# esquematico.net
KiCad netlist of a schematic drawn in EAGLE
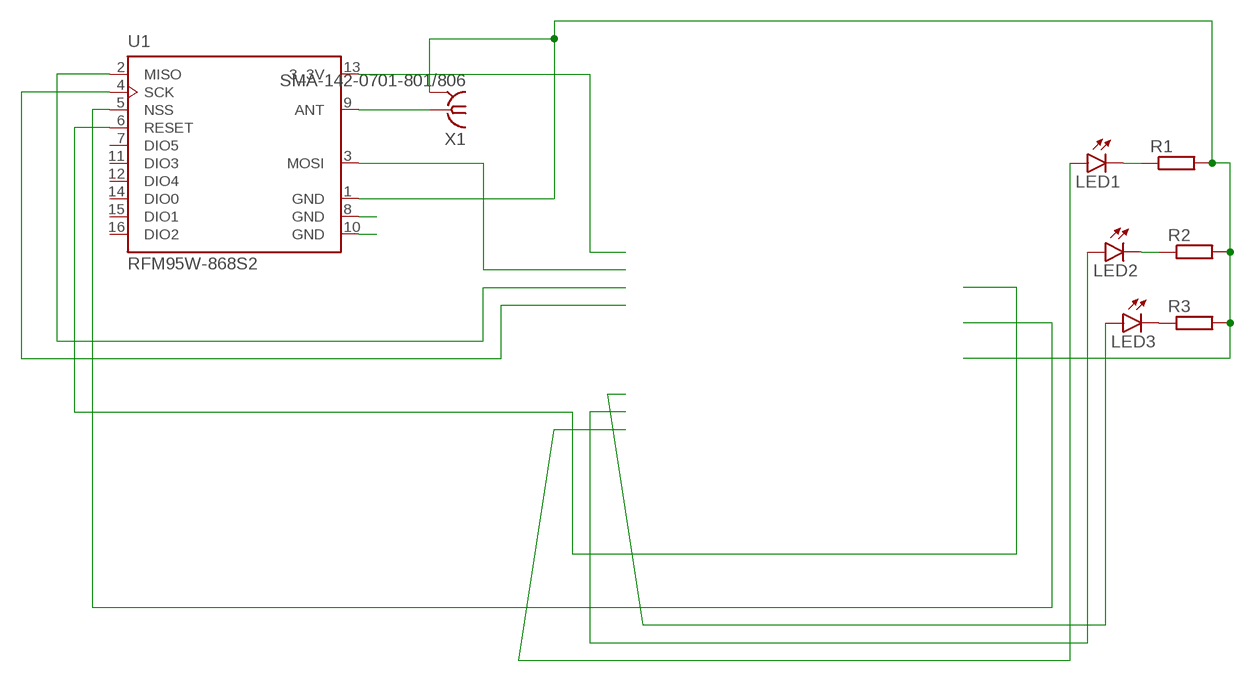
[diagram p0: schematic, sheet 1]

(export (version "E")
  (design (tool "Eeschema 10.0.6"))
  (components
    (comp (ref "LED1")
      (value "LED3MM")
      (footprint "eagle-import:LED3MM")
      (libsource (lib "eagle-import") (part "LED3MM"))
    )
    (comp (ref "LED2")
      (value "LED3MM")
      (footprint "eagle-import:LED3MM")
      (libsource (lib "eagle-import") (part "LED3MM"))
    )
    (comp (ref "LED3")
      (value "LED3MM")
      (footprint "eagle-import:LED3MM")
      (libsource (lib "eagle-import") (part "LED3MM"))
    )
    (comp (ref "R1")
      (value "R-EU_M0805")
      (footprint "eagle-import:M0805")
      (libsource (lib "eagle-import") (part "R-EU_M0805"))
    )
    (comp (ref "R2")
      (value "R-EU_M0805")
      (footprint "eagle-import:M0805")
      (libsource (lib "eagle-import") (part "R-EU_M0805"))
    )
    (comp (ref "R3")
      (value "R-EU_M0805")
      (footprint "eagle-import:M0805")
      (libsource (lib "eagle-import") (part "R-EU_M0805"))
    )
    (comp (ref "U1")
      (value "RFM95W-868S2")
      (footprint "eagle-import:XCVR_RFM95W-868S2")
      (fields (field (name "MF") "RF"))
      (libsource (lib "eagle-import") (part "RFM95W-868S2"))
    )
    (comp (ref "X1")
      (value "SMA-142-0701-801/806")
      (footprint "eagle-import:J502-ND-142-0701-801_806")
      (fields (field (name "MF") "JOHNSON COMPONENTS") (field (name "MPN") "142-0701-801"))
      (libsource (lib "eagle-import") (part "SMA-142-0701-801/806"))
    )
  )
  (nets
    (net (code "1") (name "Net-(LED1-C)") (class "Default")
      (node (ref "LED1") (pin "K") (pinfunction "C_K") (pintype "passive"))
      (node (ref "R1") (pin "1") (pinfunction "1_1") (pintype "passive"))
    )
    (net (code "2") (name "Net-(LED2-C)") (class "Default")
      (node (ref "LED2") (pin "K") (pinfunction "C_K") (pintype "passive"))
      (node (ref "R2") (pin "1") (pinfunction "1_1") (pintype "passive"))
    )
    (net (code "3") (name "Net-(LED3-C)") (class "Default")
      (node (ref "LED3") (pin "K") (pinfunction "C_K") (pintype "passive"))
      (node (ref "R3") (pin "1") (pinfunction "1_1") (pintype "passive"))
    )
    (net (code "4") (name "Net-(R1-Pad2)") (class "Default")
      (node (ref "R1") (pin "2") (pinfunction "2_2") (pintype "passive"))
      (node (ref "R2") (pin "2") (pinfunction "2_2") (pintype "passive"))
      (node (ref "R3") (pin "2") (pinfunction "2_2") (pintype "passive"))
      (node (ref "U1") (pin "1") (pinfunction "GND_1") (pintype "power_in"))
      (node (ref "X1") (pin "G@1") (pinfunction "2_G@1") (pintype "passive"))
      (node (ref "X1") (pin "G@2") (pinfunction "2_G@2") (pintype "passive"))
      (node (ref "X1") (pin "G@3") (pinfunction "2_G@3") (pintype "passive"))
      (node (ref "X1") (pin "G@4") (pinfunction "2_G@4") (pintype "passive"))
    )
    (net (code "5") (name "Net-(U1-ANT)") (class "Default")
      (node (ref "U1") (pin "9") (pinfunction "ANT_9") (pintype "passive"))
      (node (ref "X1") (pin "1") (pinfunction "1_1") (pintype "passive"))
    )
    (net (code "6") (name "unconnected-(LED1-PadA)") (class "Default")
      (node (ref "LED1") (pin "A") (pinfunction "A_A") (pintype "passive"))
    )
    (net (code "7") (name "unconnected-(LED2-PadA)") (class "Default")
      (node (ref "LED2") (pin "A") (pinfunction "A_A") (pintype "passive"))
    )
    (net (code "8") (name "unconnected-(LED3-PadA)") (class "Default")
      (node (ref "LED3") (pin "A") (pinfunction "A_A") (pintype "passive"))
    )
    (net (code "9") (name "unconnected-(U1-3_3V-Pad13)") (class "Default")
      (node (ref "U1") (pin "13") (pinfunction "3_3V_13") (pintype "power_in"))
    )
    (net (code "10") (name "unconnected-(U1-DIO0-Pad14)") (class "Default")
      (node (ref "U1") (pin "14") (pinfunction "DIO0_14") (pintype "bidirectional"))
    )
    (net (code "11") (name "unconnected-(U1-DIO1-Pad15)") (class "Default")
      (node (ref "U1") (pin "15") (pinfunction "DIO1_15") (pintype "bidirectional"))
    )
    (net (code "12") (name "unconnected-(U1-DIO2-Pad16)") (class "Default")
      (node (ref "U1") (pin "16") (pinfunction "DIO2_16") (pintype "bidirectional"))
    )
    (net (code "13") (name "unconnected-(U1-DIO3-Pad11)") (class "Default")
      (node (ref "U1") (pin "11") (pinfunction "DIO3_11") (pintype "bidirectional"))
    )
    (net (code "14") (name "unconnected-(U1-DIO4-Pad12)") (class "Default")
      (node (ref "U1") (pin "12") (pinfunction "DIO4_12") (pintype "bidirectional"))
    )
    (net (code "15") (name "unconnected-(U1-DIO5-Pad7)") (class "Default")
      (node (ref "U1") (pin "7") (pinfunction "DIO5_7") (pintype "bidirectional"))
    )
    (net (code "16") (name "unconnected-(U1-GND-Pad8)") (class "Default")
      (node (ref "U1") (pin "8") (pinfunction "GND_8") (pintype "power_in"))
    )
    (net (code "17") (name "unconnected-(U1-GND-Pad10)") (class "Default")
      (node (ref "U1") (pin "10") (pinfunction "GND_10") (pintype "power_in"))
    )
    (net (code "18") (name "unconnected-(U1-MISO-Pad2)") (class "Default")
      (node (ref "U1") (pin "2") (pinfunction "MISO_2") (pintype "input"))
    )
    (net (code "19") (name "unconnected-(U1-MOSI-Pad3)") (class "Default")
      (node (ref "U1") (pin "3") (pinfunction "MOSI_3") (pintype "output"))
    )
    (net (code "20") (name "unconnected-(U1-NSS-Pad5)") (class "Default")
      (node (ref "U1") (pin "5") (pinfunction "NSS_5") (pintype "input"))
    )
    (net (code "21") (name "unconnected-(U1-RESET-Pad6)") (class "Default")
      (node (ref "U1") (pin "6") (pinfunction "RESET_6") (pintype "bidirectional"))
    )
    (net (code "22") (name "unconnected-(U1-SCK-Pad4)") (class "Default")
      (node (ref "U1") (pin "4") (pinfunction "SCK_4") (pintype "input"))
    )
  )
)
